# PMU.net
KiCad netlist of a schematic drawn in Altium Designer
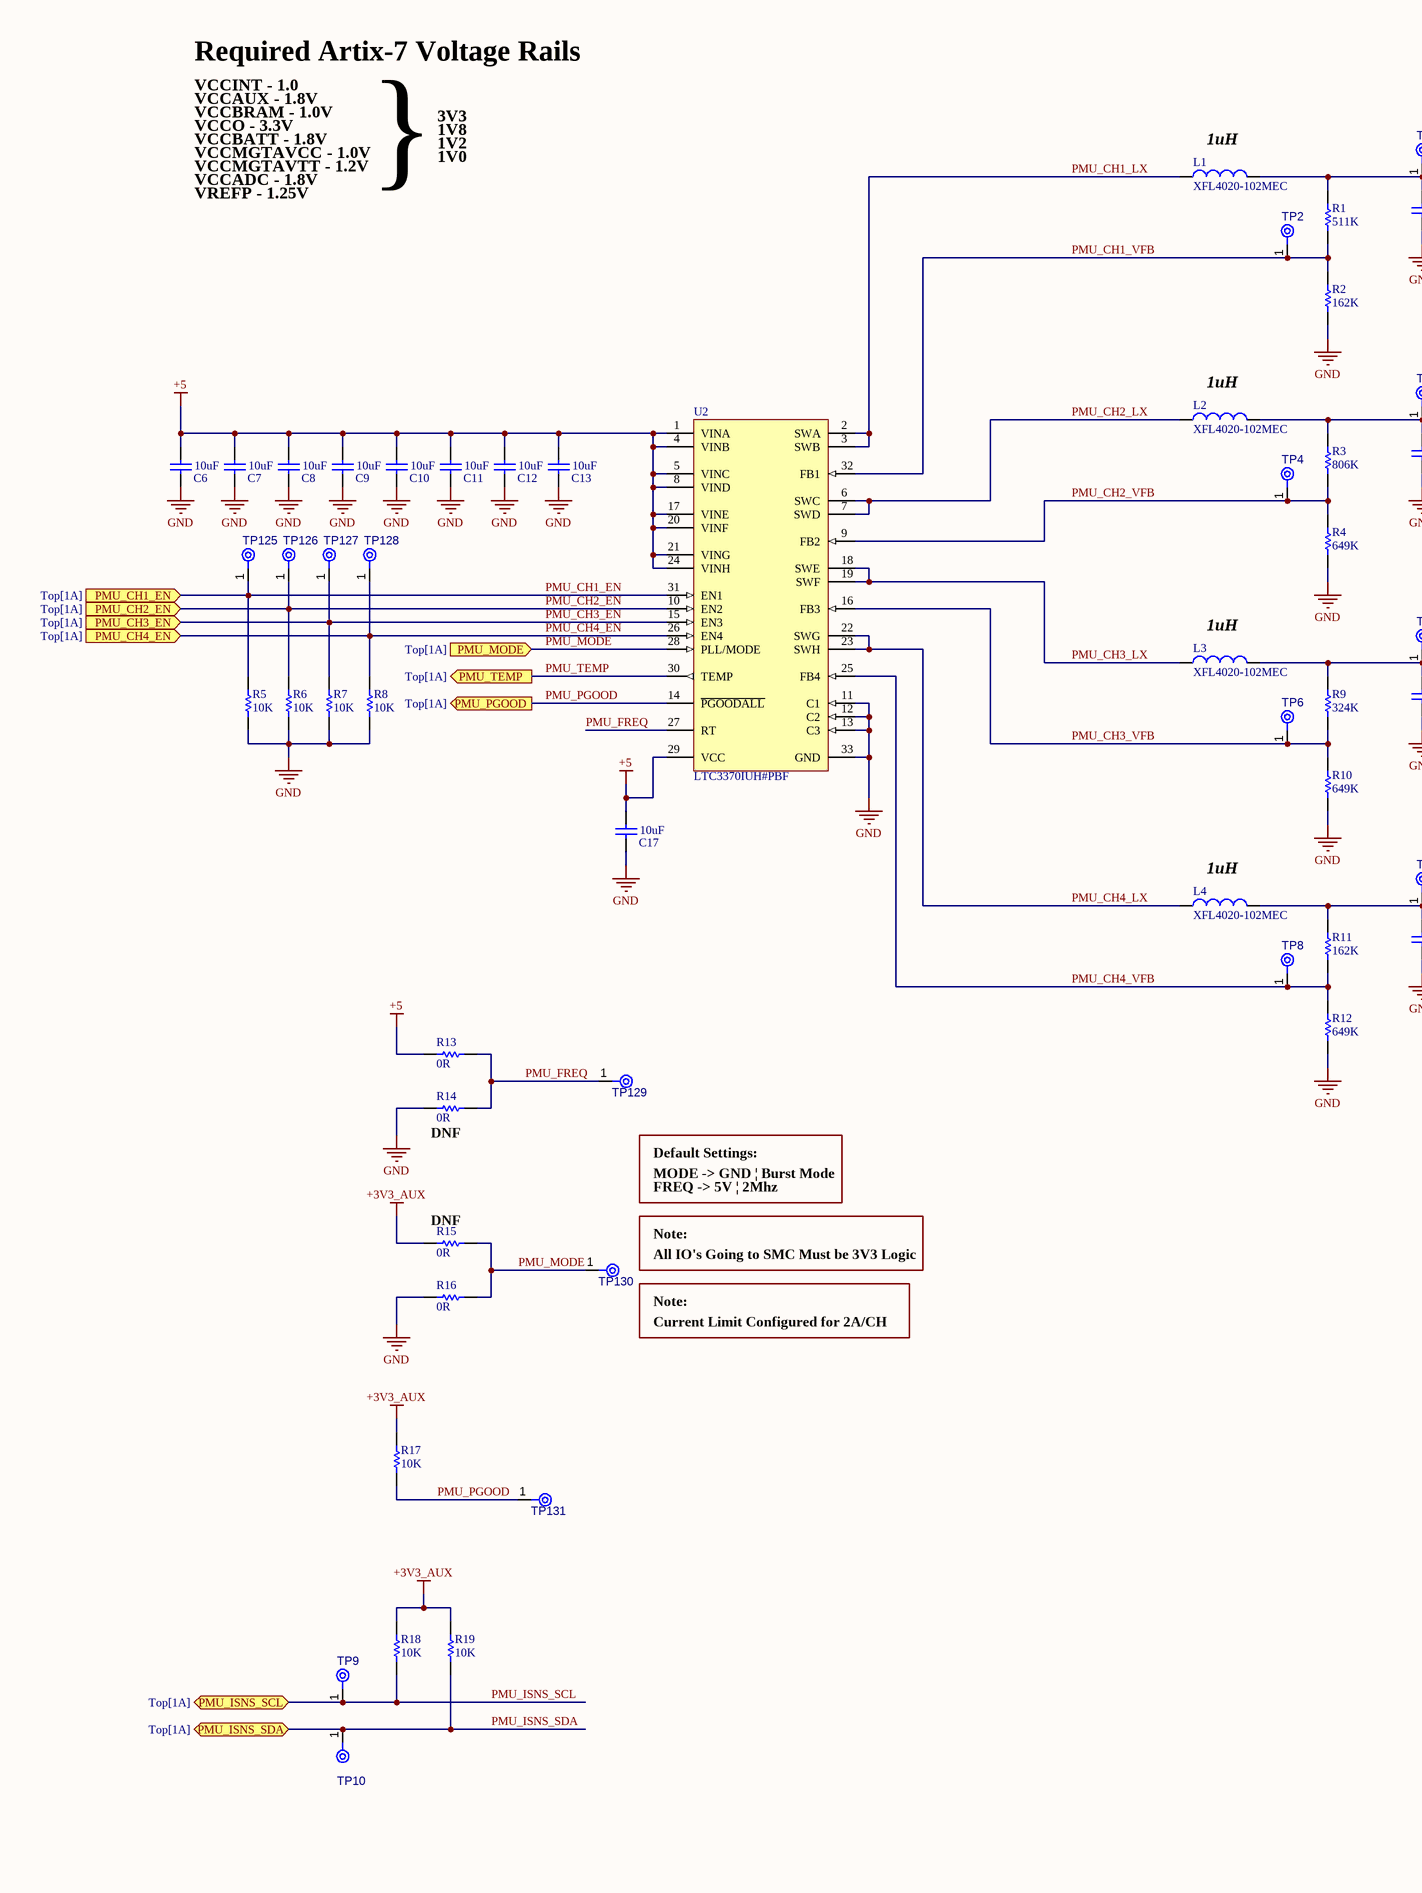
[diagram p0: PMU.SchDoc, left]
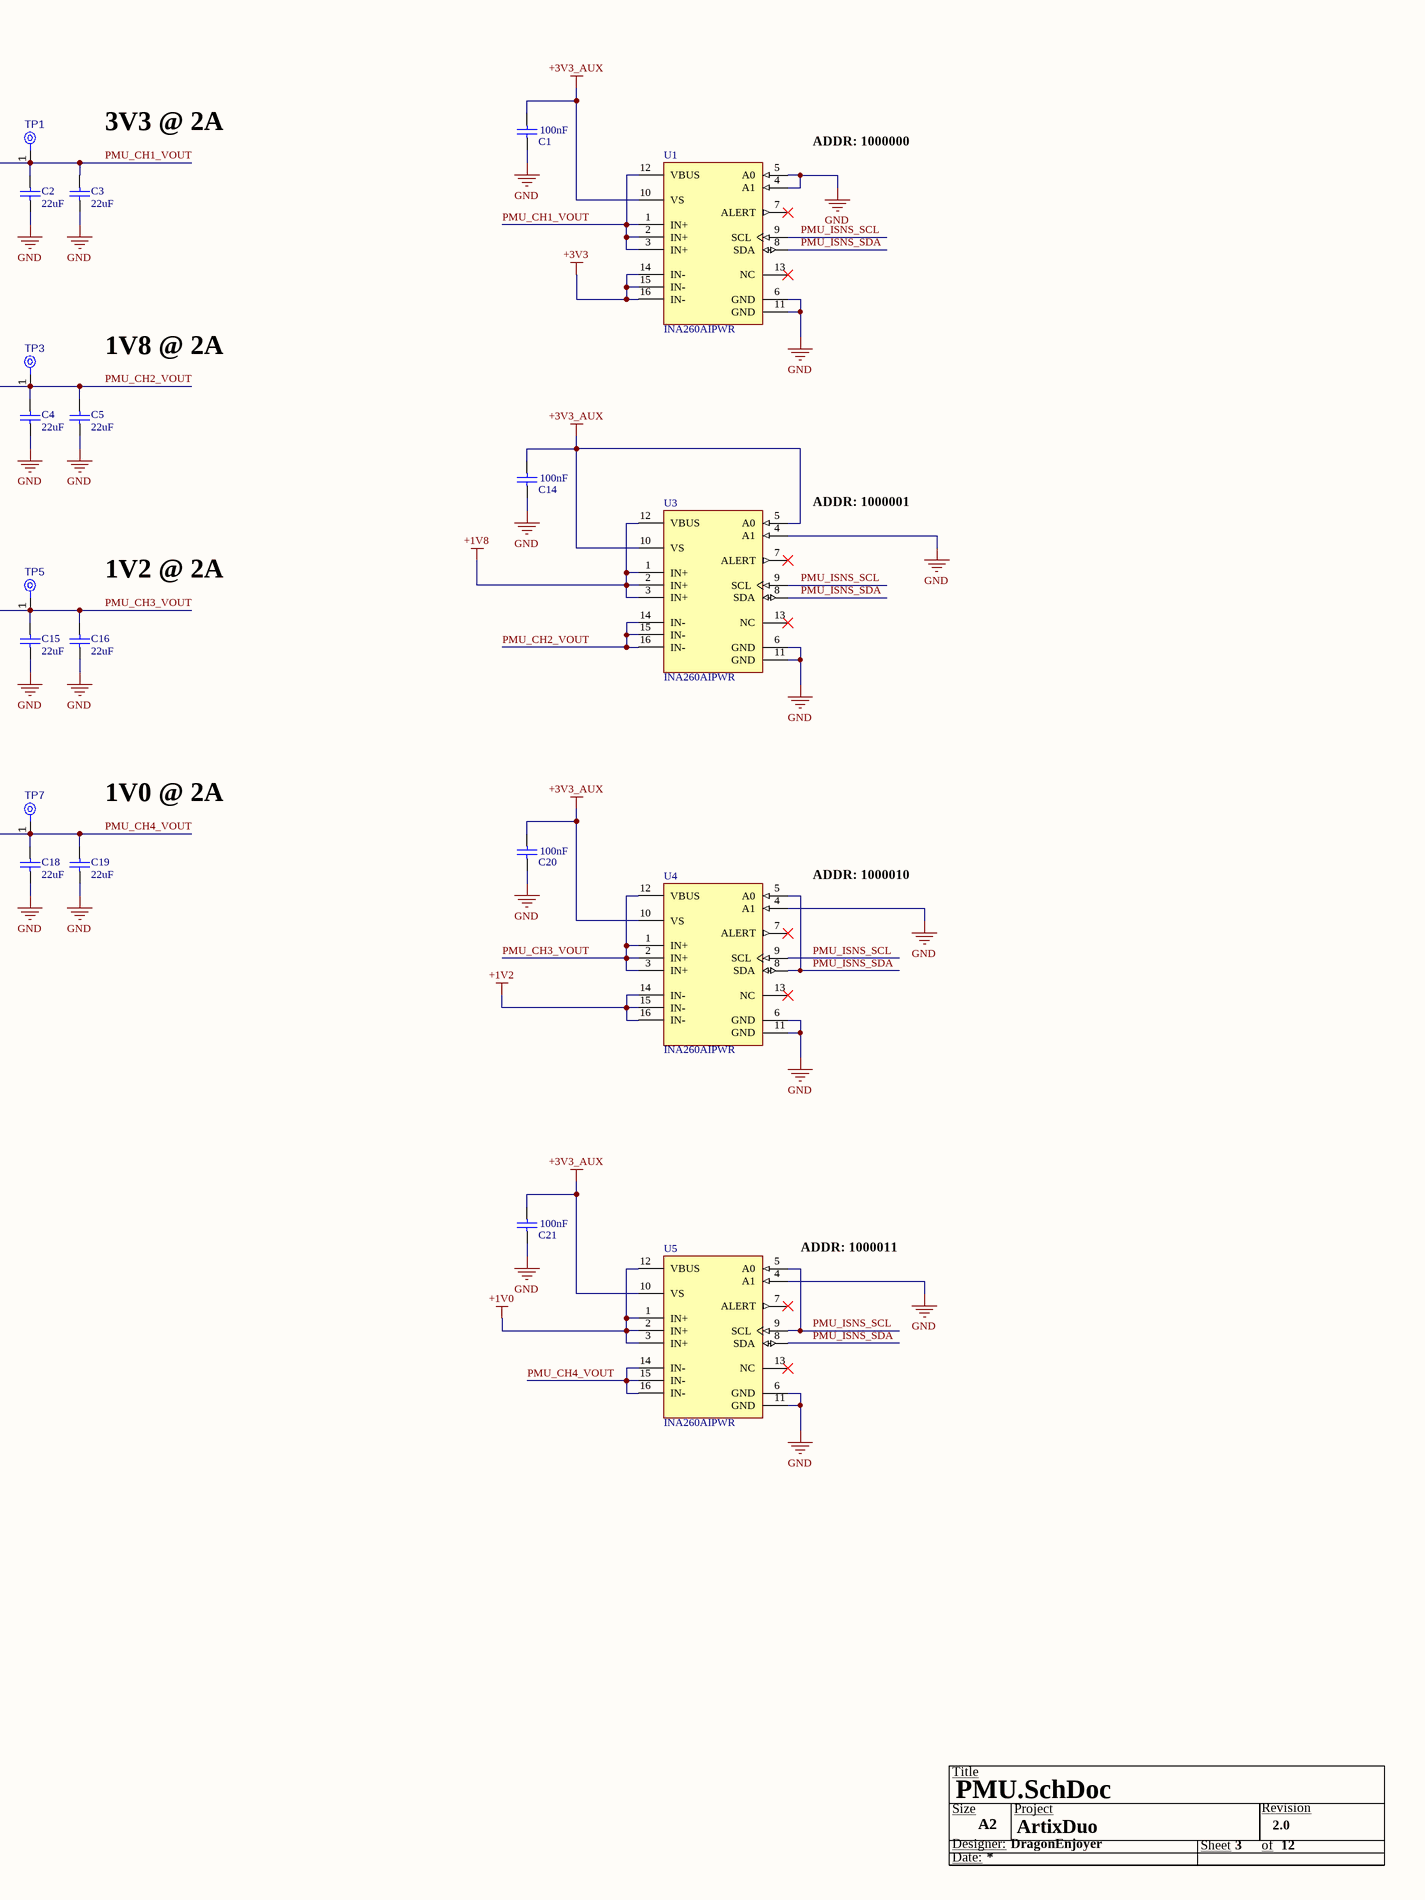
[diagram p1: PMU.SchDoc, right]

(export (version "E")
  (design (tool "Eeschema 10.0.6"))
  (components
    (comp (ref "C1")
      (value "100nF")
      (footprint "CAPC1005X05N")
      (description "Cap Ceramic 0.1uF 50V X7R 20% SMD 0402 125°C Paper T/R GRM155R71H104ME14J")
      (fields (field (name "VOLTAGE") "50V"))
      (libsource (lib "Main Workspace") (part "CAP"))
    )
    (comp (ref "C2")
      (value "22uF")
      (footprint "CAPC3216X18N")
      (description "1206 22 uF 10 V ±10% Tolerance X7R Multilayer Ceramic Capacitor")
      (fields (field (name "TOLERANCE") "10%") (field (name "Comment") "GCM31CR71A226KE02L"))
      (libsource (lib "Main Workspace") (part "CAP"))
    )
    (comp (ref "C3")
      (value "22uF")
      (footprint "CAPC3216X18N")
      (description "1206 22 uF 10 V ±10% Tolerance X7R Multilayer Ceramic Capacitor")
      (fields (field (name "TOLERANCE") "10%") (field (name "Comment") "GCM31CR71A226KE02L"))
      (libsource (lib "Main Workspace") (part "CAP"))
    )
    (comp (ref "C4")
      (value "22uF")
      (footprint "CAPC3216X18N")
      (description "1206 22 uF 10 V ±10% Tolerance X7R Multilayer Ceramic Capacitor")
      (fields (field (name "TOLERANCE") "10%") (field (name "Comment") "GCM31CR71A226KE02L"))
      (libsource (lib "Main Workspace") (part "CAP"))
    )
    (comp (ref "C5")
      (value "22uF")
      (footprint "CAPC3216X18N")
      (description "1206 22 uF 10 V ±10% Tolerance X7R Multilayer Ceramic Capacitor")
      (fields (field (name "TOLERANCE") "10%") (field (name "Comment") "GCM31CR71A226KE02L"))
      (libsource (lib "Main Workspace") (part "CAP"))
    )
    (comp (ref "C6")
      (value "10uF")
      (footprint "CAPC0805(2012)145_L")
      (description "Multilayer Ceramic Capacitor, 10 uF, 25 VDC, ± 10%, X7S, 0805 [2012 Metric] GRM21BC71E106KE01K")
      (libsource (lib "Main Workspace") (part "CAP"))
    )
    (comp (ref "C7")
      (value "10uF")
      (footprint "CAPC0805(2012)145_L")
      (description "Multilayer Ceramic Capacitor, 10 uF, 25 VDC, ± 10%, X7S, 0805 [2012 Metric] GRM21BC71E106KE01K")
      (libsource (lib "Main Workspace") (part "CAP"))
    )
    (comp (ref "C8")
      (value "10uF")
      (footprint "CAPC0805(2012)145_L")
      (description "Multilayer Ceramic Capacitor, 10 uF, 25 VDC, ± 10%, X7S, 0805 [2012 Metric] GRM21BC71E106KE01K")
      (libsource (lib "Main Workspace") (part "CAP"))
    )
    (comp (ref "C9")
      (value "10uF")
      (footprint "CAPC0805(2012)145_L")
      (description "Multilayer Ceramic Capacitor, 10 uF, 25 VDC, ± 10%, X7S, 0805 [2012 Metric] GRM21BC71E106KE01K")
      (libsource (lib "Main Workspace") (part "CAP"))
    )
    (comp (ref "C10")
      (value "10uF")
      (footprint "CAPC0805(2012)145_L")
      (description "Multilayer Ceramic Capacitor, 10 uF, 25 VDC, ± 10%, X7S, 0805 [2012 Metric] GRM21BC71E106KE01K")
      (libsource (lib "Main Workspace") (part "CAP"))
    )
    (comp (ref "C11")
      (value "10uF")
      (footprint "CAPC0805(2012)145_L")
      (description "Multilayer Ceramic Capacitor, 10 uF, 25 VDC, ± 10%, X7S, 0805 [2012 Metric] GRM21BC71E106KE01K")
      (libsource (lib "Main Workspace") (part "CAP"))
    )
    (comp (ref "C12")
      (value "10uF")
      (footprint "CAPC0805(2012)145_L")
      (description "Multilayer Ceramic Capacitor, 10 uF, 25 VDC, ± 10%, X7S, 0805 [2012 Metric] GRM21BC71E106KE01K")
      (libsource (lib "Main Workspace") (part "CAP"))
    )
    (comp (ref "C13")
      (value "10uF")
      (footprint "CAPC0805(2012)145_L")
      (description "Multilayer Ceramic Capacitor, 10 uF, 25 VDC, ± 10%, X7S, 0805 [2012 Metric] GRM21BC71E106KE01K")
      (libsource (lib "Main Workspace") (part "CAP"))
    )
    (comp (ref "C14")
      (value "100nF")
      (footprint "CAPC1005X05N")
      (description "Cap Ceramic 0.1uF 50V X7R 20% SMD 0402 125°C Paper T/R GRM155R71H104ME14J")
      (fields (field (name "VOLTAGE") "50V"))
      (libsource (lib "Main Workspace") (part "CAP"))
    )
    (comp (ref "C15")
      (value "22uF")
      (footprint "CAPC3216X18N")
      (description "1206 22 uF 10 V ±10% Tolerance X7R Multilayer Ceramic Capacitor")
      (fields (field (name "TOLERANCE") "10%") (field (name "Comment") "GCM31CR71A226KE02L"))
      (libsource (lib "Main Workspace") (part "CAP"))
    )
    (comp (ref "C16")
      (value "22uF")
      (footprint "CAPC3216X18N")
      (description "1206 22 uF 10 V ±10% Tolerance X7R Multilayer Ceramic Capacitor")
      (fields (field (name "TOLERANCE") "10%") (field (name "Comment") "GCM31CR71A226KE02L"))
      (libsource (lib "Main Workspace") (part "CAP"))
    )
    (comp (ref "C17")
      (value "10uF")
      (footprint "CAPC0805(2012)145_L")
      (description "Multilayer Ceramic Capacitor, 10 uF, 25 VDC, ± 10%, X7S, 0805 [2012 Metric] GRM21BC71E106KE01K")
      (libsource (lib "Main Workspace") (part "CAP"))
    )
    (comp (ref "C18")
      (value "22uF")
      (footprint "CAPC3216X18N")
      (description "1206 22 uF 10 V ±10% Tolerance X7R Multilayer Ceramic Capacitor")
      (fields (field (name "TOLERANCE") "10%") (field (name "Comment") "GCM31CR71A226KE02L"))
      (libsource (lib "Main Workspace") (part "CAP"))
    )
    (comp (ref "C19")
      (value "22uF")
      (footprint "CAPC3216X18N")
      (description "1206 22 uF 10 V ±10% Tolerance X7R Multilayer Ceramic Capacitor")
      (fields (field (name "TOLERANCE") "10%") (field (name "Comment") "GCM31CR71A226KE02L"))
      (libsource (lib "Main Workspace") (part "CAP"))
    )
    (comp (ref "C20")
      (value "100nF")
      (footprint "CAPC1005X05N")
      (description "Cap Ceramic 0.1uF 50V X7R 20% SMD 0402 125°C Paper T/R GRM155R71H104ME14J")
      (fields (field (name "VOLTAGE") "50V"))
      (libsource (lib "Main Workspace") (part "CAP"))
    )
    (comp (ref "C21")
      (value "100nF")
      (footprint "CAPC1005X05N")
      (description "Cap Ceramic 0.1uF 50V X7R 20% SMD 0402 125°C Paper T/R GRM155R71H104ME14J")
      (fields (field (name "VOLTAGE") "50V"))
      (libsource (lib "Main Workspace") (part "CAP"))
    )
    (comp (ref "L1")
      (value "XFL4020-102MEC")
      (footprint "COIL-XFL4020_V")
      (description "Shielded Power Inductor, 1 uH, 64 MHz, -40 to 125 degC, 2-Pin SMD, RoHS, Tape and Reel")
      (fields (field (name "MANUFACTURER") "Coilcraft") (field (name "TOLERANCE") "20%"))
      (libsource (lib "Altium Content Vault") (part "IND-2"))
    )
    (comp (ref "L2")
      (value "XFL4020-102MEC")
      (footprint "COIL-XFL4020_V")
      (description "Shielded Power Inductor, 1 uH, 64 MHz, -40 to 125 degC, 2-Pin SMD, RoHS, Tape and Reel")
      (fields (field (name "MANUFACTURER") "Coilcraft") (field (name "TOLERANCE") "20%"))
      (libsource (lib "Altium Content Vault") (part "IND-2"))
    )
    (comp (ref "L3")
      (value "XFL4020-102MEC")
      (footprint "COIL-XFL4020_V")
      (description "Shielded Power Inductor, 1 uH, 64 MHz, -40 to 125 degC, 2-Pin SMD, RoHS, Tape and Reel")
      (fields (field (name "MANUFACTURER") "Coilcraft") (field (name "TOLERANCE") "20%"))
      (libsource (lib "Altium Content Vault") (part "IND-2"))
    )
    (comp (ref "L4")
      (value "XFL4020-102MEC")
      (footprint "COIL-XFL4020_V")
      (description "Shielded Power Inductor, 1 uH, 64 MHz, -40 to 125 degC, 2-Pin SMD, RoHS, Tape and Reel")
      (fields (field (name "MANUFACTURER") "Coilcraft") (field (name "TOLERANCE") "20%"))
      (libsource (lib "Altium Content Vault") (part "IND-2"))
    )
    (comp (ref "R1")
      (value "511K")
      (footprint "RESC1005X40X25NL05T10")
      (description "RC0402FR-07511KL")
      (fields (field (name "MANUFACTURER") "Yageo / Phycomp"))
      (libsource (lib "Altium Content Vault") (part "RES"))
    )
    (comp (ref "R2")
      (value "162K")
      (footprint "RESC1005X40X25NL05T10")
      (description "RC0402FR-07162KL")
      (fields (field (name "MANUFACTURER") "Yageo / Phycomp"))
      (libsource (lib "Altium Content Vault") (part "RES"))
    )
    (comp (ref "R3")
      (value "806K")
      (footprint "RESC1005X40X25NL05T10")
      (description "RC0402FR-07806KL")
      (fields (field (name "MANUFACTURER") "Yageo / Phycomp"))
      (libsource (lib "Altium Content Vault") (part "RES"))
    )
    (comp (ref "R4")
      (value "649K")
      (footprint "RESC1005X40X25NL05T10")
      (description "RC0402FR-07649KL")
      (fields (field (name "MANUFACTURER") "Yageo / Phycomp"))
      (libsource (lib "Altium Content Vault") (part "RES"))
    )
    (comp (ref "R5")
      (value "10K")
      (footprint "RESC1005X40X25NL05T10")
      (description "RC0402FR-0710KL")
      (fields (field (name "MANUFACTURER") "Yageo / Phycomp"))
      (libsource (lib "Altium Content Vault") (part "RES"))
    )
    (comp (ref "R6")
      (value "10K")
      (footprint "RESC1005X40X25NL05T10")
      (description "RC0402FR-0710KL")
      (fields (field (name "MANUFACTURER") "Yageo / Phycomp"))
      (libsource (lib "Altium Content Vault") (part "RES"))
    )
    (comp (ref "R7")
      (value "10K")
      (footprint "RESC1005X40X25NL05T10")
      (description "RC0402FR-0710KL")
      (fields (field (name "MANUFACTURER") "Yageo / Phycomp"))
      (libsource (lib "Altium Content Vault") (part "RES"))
    )
    (comp (ref "R8")
      (value "10K")
      (footprint "RESC1005X40X25NL05T10")
      (description "RC0402FR-0710KL")
      (fields (field (name "MANUFACTURER") "Yageo / Phycomp"))
      (libsource (lib "Altium Content Vault") (part "RES"))
    )
    (comp (ref "R9")
      (value "324K")
      (footprint "RESC1005X40X25NL05T10")
      (description "RC0402FR-07324KL")
      (fields (field (name "MANUFACTURER") "Yageo"))
      (libsource (lib "Altium Content Vault") (part "RES"))
    )
    (comp (ref "R10")
      (value "649K")
      (footprint "RESC1005X40X25NL05T10")
      (description "RC0402FR-07649KL")
      (fields (field (name "MANUFACTURER") "Yageo / Phycomp"))
      (libsource (lib "Altium Content Vault") (part "RES"))
    )
    (comp (ref "R11")
      (value "162K")
      (footprint "RESC1005X40X25NL05T10")
      (description "RC0402FR-07162KL")
      (fields (field (name "MANUFACTURER") "Yageo / Phycomp"))
      (libsource (lib "Altium Content Vault") (part "RES"))
    )
    (comp (ref "R12")
      (value "649K")
      (footprint "RESC1005X40X25NL05T10")
      (description "RC0402FR-07649KL")
      (fields (field (name "MANUFACTURER") "Yageo / Phycomp"))
      (libsource (lib "Altium Content Vault") (part "RES"))
    )
    (comp (ref "R13")
      (value "0R")
      (footprint "RESC1005X40X25NL05T10")
      (description "RC0402JR-070RL")
      (fields (field (name "MANUFACTURER") "Yageo / Phycomp"))
      (libsource (lib "Altium Content Vault") (part "RES"))
    )
    (comp (ref "R14")
      (value "0R")
      (footprint "RESC1005X40X25NL05T10")
      (description "RC0402JR-070RL")
      (fields (field (name "MANUFACTURER") "Yageo / Phycomp"))
      (libsource (lib "Altium Content Vault") (part "RES"))
    )
    (comp (ref "R15")
      (value "0R")
      (footprint "RESC1005X40X25NL05T10")
      (description "RC0402JR-070RL")
      (fields (field (name "MANUFACTURER") "Yageo / Phycomp"))
      (libsource (lib "Altium Content Vault") (part "RES"))
    )
    (comp (ref "R16")
      (value "0R")
      (footprint "RESC1005X40X25NL05T10")
      (description "RC0402JR-070RL")
      (fields (field (name "MANUFACTURER") "Yageo / Phycomp"))
      (libsource (lib "Altium Content Vault") (part "RES"))
    )
    (comp (ref "R17")
      (value "10K")
      (footprint "RESC1005X40X25NL05T10")
      (description "RC0402FR-0710KL")
      (fields (field (name "MANUFACTURER") "Yageo / Phycomp"))
      (libsource (lib "Altium Content Vault") (part "RES"))
    )
    (comp (ref "R18")
      (value "10K")
      (footprint "RESC1005X40X25NL05T10")
      (description "RC0402FR-0710KL")
      (fields (field (name "MANUFACTURER") "Yageo / Phycomp"))
      (libsource (lib "Altium Content Vault") (part "RES"))
    )
    (comp (ref "R19")
      (value "10K")
      (footprint "RESC1005X40X25NL05T10")
      (description "RC0402FR-0710KL")
      (fields (field (name "MANUFACTURER") "Yageo / Phycomp"))
      (libsource (lib "Altium Content Vault") (part "RES"))
    )
    (comp (ref "TP1")
      (value "TPAD6R")
      (footprint "TP06R")
      (description "0.6mm round")
      (libsource (lib "Main Workspace") (part "CMP-001-0001-4"))
    )
    (comp (ref "TP2")
      (value "TPAD6R")
      (footprint "TP06R")
      (description "0.6mm round")
      (libsource (lib "Main Workspace") (part "CMP-001-0001-4"))
    )
    (comp (ref "TP3")
      (value "TPAD6R")
      (footprint "TP06R")
      (description "0.6mm round")
      (libsource (lib "Main Workspace") (part "CMP-001-0001-4"))
    )
    (comp (ref "TP4")
      (value "TPAD6R")
      (footprint "TP06R")
      (description "0.6mm round")
      (libsource (lib "Main Workspace") (part "CMP-001-0001-4"))
    )
    (comp (ref "TP5")
      (value "TPAD6R")
      (footprint "TP06R")
      (description "0.6mm round")
      (libsource (lib "Main Workspace") (part "CMP-001-0001-4"))
    )
    (comp (ref "TP6")
      (value "TPAD6R")
      (footprint "TP06R")
      (description "0.6mm round")
      (libsource (lib "Main Workspace") (part "CMP-001-0001-4"))
    )
    (comp (ref "TP7")
      (value "TPAD6R")
      (footprint "TP06R")
      (description "0.6mm round")
      (libsource (lib "Main Workspace") (part "CMP-001-0001-4"))
    )
    (comp (ref "TP8")
      (value "TPAD6R")
      (footprint "TP06R")
      (description "0.6mm round")
      (libsource (lib "Main Workspace") (part "CMP-001-0001-4"))
    )
    (comp (ref "TP9")
      (value "TPAD6R")
      (footprint "TP06R")
      (description "0.6mm round")
      (libsource (lib "Main Workspace") (part "CMP-001-0001-4"))
    )
    (comp (ref "TP10")
      (value "TPAD6R")
      (footprint "TP06R")
      (description "0.6mm round")
      (libsource (lib "Main Workspace") (part "CMP-001-0001-4"))
    )
    (comp (ref "TP125")
      (value "TPAD6R")
      (footprint "TP06R")
      (description "0.6mm round")
      (libsource (lib "Main Workspace") (part "CMP-001-0001-4"))
    )
    (comp (ref "TP126")
      (value "TPAD6R")
      (footprint "TP06R")
      (description "0.6mm round")
      (libsource (lib "Main Workspace") (part "CMP-001-0001-4"))
    )
    (comp (ref "TP127")
      (value "TPAD6R")
      (footprint "TP06R")
      (description "0.6mm round")
      (libsource (lib "Main Workspace") (part "CMP-001-0001-4"))
    )
    (comp (ref "TP128")
      (value "TPAD6R")
      (footprint "TP06R")
      (description "0.6mm round")
      (libsource (lib "Main Workspace") (part "CMP-001-0001-4"))
    )
    (comp (ref "TP129")
      (value "TPAD6R")
      (footprint "TP06R")
      (description "0.6mm round")
      (libsource (lib "Main Workspace") (part "CMP-001-0001-4"))
    )
    (comp (ref "TP130")
      (value "TPAD6R")
      (footprint "TP06R")
      (description "0.6mm round")
      (libsource (lib "Main Workspace") (part "CMP-001-0001-4"))
    )
    (comp (ref "TP131")
      (value "TPAD6R")
      (footprint "TP06R")
      (description "0.6mm round")
      (libsource (lib "Main Workspace") (part "CMP-001-0001-4"))
    )
    (comp (ref "U1")
      (value "INA260AIPWR")
      (footprint "FP-PW0016A-IPC_B")
      (description "IC MONITOR PWR/CURR 16TSSOP")
      (fields
        (field (name "MANUFACTURER") "Texas Instruments")
        (field (name "OCTOPART") "https://octopart.com/ina260aipwr-texas+instruments-75199489")
      )
      (libsource (lib "Altium Content Vault") (part "fcceeca0fd405d0f0207f40a7ff7922"))
    )
    (comp (ref "U2")
      (value "LTC3370IUH#PBF")
      (footprint "QFN50P500X500X80_HS-33N")
      (libsource (lib "Main Workspace") (part "LT-LTC3370-UH-32"))
    )
    (comp (ref "U3")
      (value "INA260AIPWR")
      (footprint "FP-PW0016A-IPC_B")
      (description "IC MONITOR PWR/CURR 16TSSOP")
      (fields
        (field (name "MANUFACTURER") "Texas Instruments")
        (field (name "OCTOPART") "https://octopart.com/ina260aipwr-texas+instruments-75199489")
      )
      (libsource (lib "Altium Content Vault") (part "fcceeca0fd405d0f0207f40a7ff7922"))
    )
    (comp (ref "U4")
      (value "INA260AIPWR")
      (footprint "FP-PW0016A-IPC_B")
      (description "IC MONITOR PWR/CURR 16TSSOP")
      (fields
        (field (name "MANUFACTURER") "Texas Instruments")
        (field (name "OCTOPART") "https://octopart.com/ina260aipwr-texas+instruments-75199489")
      )
      (libsource (lib "Altium Content Vault") (part "fcceeca0fd405d0f0207f40a7ff7922"))
    )
    (comp (ref "U5")
      (value "INA260AIPWR")
      (footprint "FP-PW0016A-IPC_B")
      (description "IC MONITOR PWR/CURR 16TSSOP")
      (fields
        (field (name "MANUFACTURER") "Texas Instruments")
        (field (name "OCTOPART") "https://octopart.com/ina260aipwr-texas+instruments-75199489")
      )
      (libsource (lib "Altium Content Vault") (part "fcceeca0fd405d0f0207f40a7ff7922"))
    )
  )
  (nets
    (net (code "1") (name "+1V0") (class "Default")
      (node (ref "U5") (pin "1") (pinfunction "IN+_1") (pintype "passive"))
      (node (ref "U5") (pin "12") (pinfunction "VBUS_12") (pintype "passive"))
      (node (ref "U5") (pin "2") (pinfunction "IN+_2") (pintype "passive"))
      (node (ref "U5") (pin "3") (pinfunction "IN+_3") (pintype "passive"))
    )
    (net (code "2") (name "+1V2") (class "Default")
      (node (ref "U4") (pin "14") (pinfunction "IN-_14") (pintype "passive"))
      (node (ref "U4") (pin "15") (pinfunction "IN-_15") (pintype "passive"))
      (node (ref "U4") (pin "16") (pinfunction "IN-_16") (pintype "passive"))
    )
    (net (code "3") (name "+1V8") (class "Default")
      (node (ref "U3") (pin "1") (pinfunction "IN+_1") (pintype "passive"))
      (node (ref "U3") (pin "12") (pinfunction "VBUS_12") (pintype "passive"))
      (node (ref "U3") (pin "2") (pinfunction "IN+_2") (pintype "passive"))
      (node (ref "U3") (pin "3") (pinfunction "IN+_3") (pintype "passive"))
    )
    (net (code "4") (name "+3V3") (class "Default")
      (node (ref "U1") (pin "14") (pinfunction "IN-_14") (pintype "passive"))
      (node (ref "U1") (pin "15") (pinfunction "IN-_15") (pintype "passive"))
      (node (ref "U1") (pin "16") (pinfunction "IN-_16") (pintype "passive"))
    )
    (net (code "5") (name "+3V3_AUX") (class "Default")
      (node (ref "C1") (pin "2") (pinfunction "2_2") (pintype "passive"))
      (node (ref "C14") (pin "2") (pinfunction "2_2") (pintype "passive"))
      (node (ref "C20") (pin "2") (pinfunction "2_2") (pintype "passive"))
      (node (ref "C21") (pin "2") (pinfunction "2_2") (pintype "passive"))
      (node (ref "R15") (pin "1") (pinfunction "1_1") (pintype "passive"))
      (node (ref "R17") (pin "2") (pinfunction "2_2") (pintype "passive"))
      (node (ref "R18") (pin "2") (pinfunction "2_2") (pintype "passive"))
      (node (ref "R19") (pin "2") (pinfunction "2_2") (pintype "passive"))
      (node (ref "U1") (pin "10") (pinfunction "VS_10") (pintype "passive"))
      (node (ref "U3") (pin "10") (pinfunction "VS_10") (pintype "passive"))
      (node (ref "U3") (pin "5") (pinfunction "A0_5") (pintype "input"))
      (node (ref "U4") (pin "10") (pinfunction "VS_10") (pintype "passive"))
      (node (ref "U5") (pin "10") (pinfunction "VS_10") (pintype "passive"))
    )
    (net (code "6") (name "+5") (class "Default")
      (node (ref "C10") (pin "2") (pinfunction "2_2") (pintype "passive"))
      (node (ref "C11") (pin "2") (pinfunction "2_2") (pintype "passive"))
      (node (ref "C12") (pin "2") (pinfunction "2_2") (pintype "passive"))
      (node (ref "C13") (pin "2") (pinfunction "2_2") (pintype "passive"))
      (node (ref "C17") (pin "2") (pinfunction "2_2") (pintype "passive"))
      (node (ref "C6") (pin "2") (pinfunction "2_2") (pintype "passive"))
      (node (ref "C7") (pin "2") (pinfunction "2_2") (pintype "passive"))
      (node (ref "C8") (pin "2") (pinfunction "2_2") (pintype "passive"))
      (node (ref "C9") (pin "2") (pinfunction "2_2") (pintype "passive"))
      (node (ref "R13") (pin "1") (pinfunction "1_1") (pintype "passive"))
      (node (ref "U2") (pin "1") (pinfunction "VINA_1") (pintype "power_in"))
      (node (ref "U2") (pin "17") (pinfunction "VINE_17") (pintype "power_in"))
      (node (ref "U2") (pin "20") (pinfunction "VINF_20") (pintype "power_in"))
      (node (ref "U2") (pin "21") (pinfunction "VING_21") (pintype "power_in"))
      (node (ref "U2") (pin "24") (pinfunction "VINH_24") (pintype "power_in"))
      (node (ref "U2") (pin "29") (pinfunction "VCC_29") (pintype "power_in"))
      (node (ref "U2") (pin "4") (pinfunction "VINB_4") (pintype "power_in"))
      (node (ref "U2") (pin "5") (pinfunction "VINC_5") (pintype "power_in"))
      (node (ref "U2") (pin "8") (pinfunction "VIND_8") (pintype "power_in"))
    )
    (net (code "7") (name "/PMU_CH1_EN") (class "Default")
      (node (ref "R5") (pin "2") (pinfunction "2_2") (pintype "passive"))
      (node (ref "TP125") (pin "1") (pinfunction "TP_1") (pintype "passive"))
      (node (ref "U2") (pin "31") (pinfunction "EN1_31") (pintype "input"))
    )
    (net (code "8") (name "/PMU_CH1_LX") (class "Default")
      (node (ref "L1") (pin "1") (pinfunction "1_1") (pintype "passive"))
      (node (ref "U2") (pin "2") (pinfunction "SWA_2") (pintype "power_in"))
      (node (ref "U2") (pin "3") (pinfunction "SWB_3") (pintype "power_in"))
    )
    (net (code "9") (name "/PMU_CH1_VFB") (class "Default")
      (node (ref "R1") (pin "1") (pinfunction "1_1") (pintype "passive"))
      (node (ref "R2") (pin "1") (pinfunction "1_1") (pintype "passive"))
      (node (ref "TP2") (pin "1") (pinfunction "TP_1") (pintype "passive"))
      (node (ref "U2") (pin "32") (pinfunction "FB1_32") (pintype "input"))
    )
    (net (code "10") (name "/PMU_CH1_VOUT") (class "Default")
      (node (ref "C2") (pin "2") (pinfunction "2_2") (pintype "passive"))
      (node (ref "C3") (pin "2") (pinfunction "2_2") (pintype "passive"))
      (node (ref "L1") (pin "2") (pinfunction "2_2") (pintype "passive"))
      (node (ref "R1") (pin "2") (pinfunction "2_2") (pintype "passive"))
      (node (ref "TP1") (pin "1") (pinfunction "TP_1") (pintype "passive"))
      (node (ref "U1") (pin "1") (pinfunction "IN+_1") (pintype "passive"))
      (node (ref "U1") (pin "12") (pinfunction "VBUS_12") (pintype "passive"))
      (node (ref "U1") (pin "2") (pinfunction "IN+_2") (pintype "passive"))
      (node (ref "U1") (pin "3") (pinfunction "IN+_3") (pintype "passive"))
    )
    (net (code "11") (name "/PMU_CH2_EN") (class "Default")
      (node (ref "R6") (pin "2") (pinfunction "2_2") (pintype "passive"))
      (node (ref "TP126") (pin "1") (pinfunction "TP_1") (pintype "passive"))
      (node (ref "U2") (pin "10") (pinfunction "EN2_10") (pintype "input"))
    )
    (net (code "12") (name "/PMU_CH2_LX") (class "Default")
      (node (ref "L2") (pin "1") (pinfunction "1_1") (pintype "passive"))
      (node (ref "U2") (pin "6") (pinfunction "SWC_6") (pintype "power_in"))
      (node (ref "U2") (pin "7") (pinfunction "SWD_7") (pintype "power_in"))
    )
    (net (code "13") (name "/PMU_CH2_VFB") (class "Default")
      (node (ref "R3") (pin "1") (pinfunction "1_1") (pintype "passive"))
      (node (ref "R4") (pin "2") (pinfunction "2_2") (pintype "passive"))
      (node (ref "TP4") (pin "1") (pinfunction "TP_1") (pintype "passive"))
      (node (ref "U2") (pin "9") (pinfunction "FB2_9") (pintype "input"))
    )
    (net (code "14") (name "/PMU_CH2_VOUT") (class "Default")
      (node (ref "C4") (pin "2") (pinfunction "2_2") (pintype "passive"))
      (node (ref "C5") (pin "2") (pinfunction "2_2") (pintype "passive"))
      (node (ref "L2") (pin "2") (pinfunction "2_2") (pintype "passive"))
      (node (ref "R3") (pin "2") (pinfunction "2_2") (pintype "passive"))
      (node (ref "TP3") (pin "1") (pinfunction "TP_1") (pintype "passive"))
      (node (ref "U3") (pin "14") (pinfunction "IN-_14") (pintype "passive"))
      (node (ref "U3") (pin "15") (pinfunction "IN-_15") (pintype "passive"))
      (node (ref "U3") (pin "16") (pinfunction "IN-_16") (pintype "passive"))
    )
    (net (code "15") (name "/PMU_CH3_EN") (class "Default")
      (node (ref "R7") (pin "2") (pinfunction "2_2") (pintype "passive"))
      (node (ref "TP127") (pin "1") (pinfunction "TP_1") (pintype "passive"))
      (node (ref "U2") (pin "15") (pinfunction "EN3_15") (pintype "input"))
    )
    (net (code "16") (name "/PMU_CH3_LX") (class "Default")
      (node (ref "L3") (pin "1") (pinfunction "1_1") (pintype "passive"))
      (node (ref "U2") (pin "18") (pinfunction "SWE_18") (pintype "power_in"))
      (node (ref "U2") (pin "19") (pinfunction "SWF_19") (pintype "power_in"))
    )
    (net (code "17") (name "/PMU_CH3_VFB") (class "Default")
      (node (ref "R10") (pin "2") (pinfunction "2_2") (pintype "passive"))
      (node (ref "R9") (pin "1") (pinfunction "1_1") (pintype "passive"))
      (node (ref "TP6") (pin "1") (pinfunction "TP_1") (pintype "passive"))
      (node (ref "U2") (pin "16") (pinfunction "FB3_16") (pintype "input"))
    )
    (net (code "18") (name "/PMU_CH3_VOUT") (class "Default")
      (node (ref "C15") (pin "2") (pinfunction "2_2") (pintype "passive"))
      (node (ref "C16") (pin "2") (pinfunction "2_2") (pintype "passive"))
      (node (ref "L3") (pin "2") (pinfunction "2_2") (pintype "passive"))
      (node (ref "R9") (pin "2") (pinfunction "2_2") (pintype "passive"))
      (node (ref "TP5") (pin "1") (pinfunction "TP_1") (pintype "passive"))
      (node (ref "U4") (pin "1") (pinfunction "IN+_1") (pintype "passive"))
      (node (ref "U4") (pin "12") (pinfunction "VBUS_12") (pintype "passive"))
      (node (ref "U4") (pin "2") (pinfunction "IN+_2") (pintype "passive"))
      (node (ref "U4") (pin "3") (pinfunction "IN+_3") (pintype "passive"))
    )
    (net (code "19") (name "/PMU_CH4_EN") (class "Default")
      (node (ref "R8") (pin "2") (pinfunction "2_2") (pintype "passive"))
      (node (ref "TP128") (pin "1") (pinfunction "TP_1") (pintype "passive"))
      (node (ref "U2") (pin "26") (pinfunction "EN4_26") (pintype "input"))
    )
    (net (code "20") (name "/PMU_CH4_LX") (class "Default")
      (node (ref "L4") (pin "1") (pinfunction "1_1") (pintype "passive"))
      (node (ref "U2") (pin "22") (pinfunction "SWG_22") (pintype "power_in"))
      (node (ref "U2") (pin "23") (pinfunction "SWH_23") (pintype "power_in"))
    )
    (net (code "21") (name "/PMU_CH4_VFB") (class "Default")
      (node (ref "R11") (pin "2") (pinfunction "2_2") (pintype "passive"))
      (node (ref "R12") (pin "2") (pinfunction "2_2") (pintype "passive"))
      (node (ref "TP8") (pin "1") (pinfunction "TP_1") (pintype "passive"))
      (node (ref "U2") (pin "25") (pinfunction "FB4_25") (pintype "input"))
    )
    (net (code "22") (name "/PMU_CH4_VOUT") (class "Default")
      (node (ref "C18") (pin "2") (pinfunction "2_2") (pintype "passive"))
      (node (ref "C19") (pin "2") (pinfunction "2_2") (pintype "passive"))
      (node (ref "L4") (pin "2") (pinfunction "2_2") (pintype "passive"))
      (node (ref "R11") (pin "1") (pinfunction "1_1") (pintype "passive"))
      (node (ref "TP7") (pin "1") (pinfunction "TP_1") (pintype "passive"))
      (node (ref "U5") (pin "14") (pinfunction "IN-_14") (pintype "passive"))
      (node (ref "U5") (pin "15") (pinfunction "IN-_15") (pintype "passive"))
      (node (ref "U5") (pin "16") (pinfunction "IN-_16") (pintype "passive"))
    )
    (net (code "23") (name "/PMU_FREQ") (class "Default")
      (node (ref "R13") (pin "2") (pinfunction "2_2") (pintype "passive"))
      (node (ref "R14") (pin "2") (pinfunction "2_2") (pintype "passive"))
      (node (ref "TP129") (pin "1") (pinfunction "TP_1") (pintype "passive"))
      (node (ref "U2") (pin "27") (pinfunction "RT_27") (pintype "passive"))
    )
    (net (code "24") (name "/PMU_ISNS_SCL") (class "Default")
      (node (ref "R18") (pin "1") (pinfunction "1_1") (pintype "passive"))
      (node (ref "TP9") (pin "1") (pinfunction "TP_1") (pintype "passive"))
      (node (ref "U1") (pin "9") (pinfunction "SCL_9") (pintype "input"))
      (node (ref "U3") (pin "9") (pinfunction "SCL_9") (pintype "input"))
      (node (ref "U4") (pin "9") (pinfunction "SCL_9") (pintype "input"))
      (node (ref "U5") (pin "5") (pinfunction "A0_5") (pintype "input"))
      (node (ref "U5") (pin "9") (pinfunction "SCL_9") (pintype "input"))
    )
    (net (code "25") (name "/PMU_ISNS_SDA") (class "Default")
      (node (ref "R19") (pin "1") (pinfunction "1_1") (pintype "passive"))
      (node (ref "TP10") (pin "1") (pinfunction "TP_1") (pintype "passive"))
      (node (ref "U1") (pin "8") (pinfunction "SDA_8") (pintype "bidirectional"))
      (node (ref "U3") (pin "8") (pinfunction "SDA_8") (pintype "bidirectional"))
      (node (ref "U4") (pin "5") (pinfunction "A0_5") (pintype "input"))
      (node (ref "U4") (pin "8") (pinfunction "SDA_8") (pintype "bidirectional"))
      (node (ref "U5") (pin "8") (pinfunction "SDA_8") (pintype "bidirectional"))
    )
    (net (code "26") (name "/PMU_MODE") (class "Default")
      (node (ref "R15") (pin "2") (pinfunction "2_2") (pintype "passive"))
      (node (ref "R16") (pin "2") (pinfunction "2_2") (pintype "passive"))
      (node (ref "TP130") (pin "1") (pinfunction "TP_1") (pintype "passive"))
      (node (ref "U2") (pin "28") (pinfunction "PLL/MODE_28") (pintype "input"))
    )
    (net (code "27") (name "/PMU_PGOOD") (class "Default")
      (node (ref "R17") (pin "1") (pinfunction "1_1") (pintype "passive"))
      (node (ref "TP131") (pin "1") (pinfunction "TP_1") (pintype "passive"))
      (node (ref "U2") (pin "14") (pinfunction "~{PGOODALL}_14") (pintype "open_collector"))
    )
    (net (code "28") (name "/PMU_TEMP") (class "Default")
      (node (ref "U2") (pin "30") (pinfunction "TEMP_30") (pintype "output"))
    )
    (net (code "29") (name "GND") (class "Default")
      (node (ref "C1") (pin "1") (pinfunction "1_1") (pintype "passive"))
      (node (ref "C10") (pin "1") (pinfunction "1_1") (pintype "passive"))
      (node (ref "C11") (pin "1") (pinfunction "1_1") (pintype "passive"))
      (node (ref "C12") (pin "1") (pinfunction "1_1") (pintype "passive"))
      (node (ref "C13") (pin "1") (pinfunction "1_1") (pintype "passive"))
      (node (ref "C14") (pin "1") (pinfunction "1_1") (pintype "passive"))
      (node (ref "C15") (pin "1") (pinfunction "1_1") (pintype "passive"))
      (node (ref "C16") (pin "1") (pinfunction "1_1") (pintype "passive"))
      (node (ref "C17") (pin "1") (pinfunction "1_1") (pintype "passive"))
      (node (ref "C18") (pin "1") (pinfunction "1_1") (pintype "passive"))
      (node (ref "C19") (pin "1") (pinfunction "1_1") (pintype "passive"))
      (node (ref "C2") (pin "1") (pinfunction "1_1") (pintype "passive"))
      (node (ref "C20") (pin "1") (pinfunction "1_1") (pintype "passive"))
      (node (ref "C21") (pin "1") (pinfunction "1_1") (pintype "passive"))
      (node (ref "C3") (pin "1") (pinfunction "1_1") (pintype "passive"))
      (node (ref "C4") (pin "1") (pinfunction "1_1") (pintype "passive"))
      (node (ref "C5") (pin "1") (pinfunction "1_1") (pintype "passive"))
      (node (ref "C6") (pin "1") (pinfunction "1_1") (pintype "passive"))
      (node (ref "C7") (pin "1") (pinfunction "1_1") (pintype "passive"))
      (node (ref "C8") (pin "1") (pinfunction "1_1") (pintype "passive"))
      (node (ref "C9") (pin "1") (pinfunction "1_1") (pintype "passive"))
      (node (ref "R10") (pin "1") (pinfunction "1_1") (pintype "passive"))
      (node (ref "R12") (pin "1") (pinfunction "1_1") (pintype "passive"))
      (node (ref "R14") (pin "1") (pinfunction "1_1") (pintype "passive"))
      (node (ref "R16") (pin "1") (pinfunction "1_1") (pintype "passive"))
      (node (ref "R2") (pin "2") (pinfunction "2_2") (pintype "passive"))
      (node (ref "R4") (pin "1") (pinfunction "1_1") (pintype "passive"))
      (node (ref "R5") (pin "1") (pinfunction "1_1") (pintype "passive"))
      (node (ref "R6") (pin "1") (pinfunction "1_1") (pintype "passive"))
      (node (ref "R7") (pin "1") (pinfunction "1_1") (pintype "passive"))
      (node (ref "R8") (pin "1") (pinfunction "1_1") (pintype "passive"))
      (node (ref "U1") (pin "11") (pinfunction "GND_11") (pintype "power_in"))
      (node (ref "U1") (pin "4") (pinfunction "A1_4") (pintype "input"))
      (node (ref "U1") (pin "5") (pinfunction "A0_5") (pintype "input"))
      (node (ref "U1") (pin "6") (pinfunction "GND_6") (pintype "power_in"))
      (node (ref "U2") (pin "11") (pinfunction "C1_11") (pintype "input"))
      (node (ref "U2") (pin "12") (pinfunction "C2_12") (pintype "input"))
      (node (ref "U2") (pin "13") (pinfunction "C3_13") (pintype "input"))
      (node (ref "U2") (pin "33") (pinfunction "GND_33") (pintype "power_in"))
      (node (ref "U3") (pin "11") (pinfunction "GND_11") (pintype "power_in"))
      (node (ref "U3") (pin "4") (pinfunction "A1_4") (pintype "input"))
      (node (ref "U3") (pin "6") (pinfunction "GND_6") (pintype "power_in"))
      (node (ref "U4") (pin "11") (pinfunction "GND_11") (pintype "power_in"))
      (node (ref "U4") (pin "4") (pinfunction "A1_4") (pintype "input"))
      (node (ref "U4") (pin "6") (pinfunction "GND_6") (pintype "power_in"))
      (node (ref "U5") (pin "11") (pinfunction "GND_11") (pintype "power_in"))
      (node (ref "U5") (pin "4") (pinfunction "A1_4") (pintype "input"))
      (node (ref "U5") (pin "6") (pinfunction "GND_6") (pintype "power_in"))
    )
    (net (code "30") (name "unconnected-(U1-ALERT-Pad7)") (class "Default")
      (node (ref "U1") (pin "7") (pinfunction "ALERT_7") (pintype "output+no_connect"))
    )
    (net (code "31") (name "unconnected-(U1-NC-Pad13)") (class "Default")
      (node (ref "U1") (pin "13") (pinfunction "NC_13") (pintype "passive+no_connect"))
    )
    (net (code "32") (name "unconnected-(U3-ALERT-Pad7)") (class "Default")
      (node (ref "U3") (pin "7") (pinfunction "ALERT_7") (pintype "output+no_connect"))
    )
    (net (code "33") (name "unconnected-(U3-NC-Pad13)") (class "Default")
      (node (ref "U3") (pin "13") (pinfunction "NC_13") (pintype "passive+no_connect"))
    )
    (net (code "34") (name "unconnected-(U4-ALERT-Pad7)") (class "Default")
      (node (ref "U4") (pin "7") (pinfunction "ALERT_7") (pintype "output+no_connect"))
    )
    (net (code "35") (name "unconnected-(U4-NC-Pad13)") (class "Default")
      (node (ref "U4") (pin "13") (pinfunction "NC_13") (pintype "passive+no_connect"))
    )
    (net (code "36") (name "unconnected-(U5-ALERT-Pad7)") (class "Default")
      (node (ref "U5") (pin "7") (pinfunction "ALERT_7") (pintype "output+no_connect"))
    )
    (net (code "37") (name "unconnected-(U5-NC-Pad13)") (class "Default")
      (node (ref "U5") (pin "13") (pinfunction "NC_13") (pintype "passive+no_connect"))
    )
  )
)
